# Ethernet.net
KiCad netlist of a schematic drawn in Altium Designer
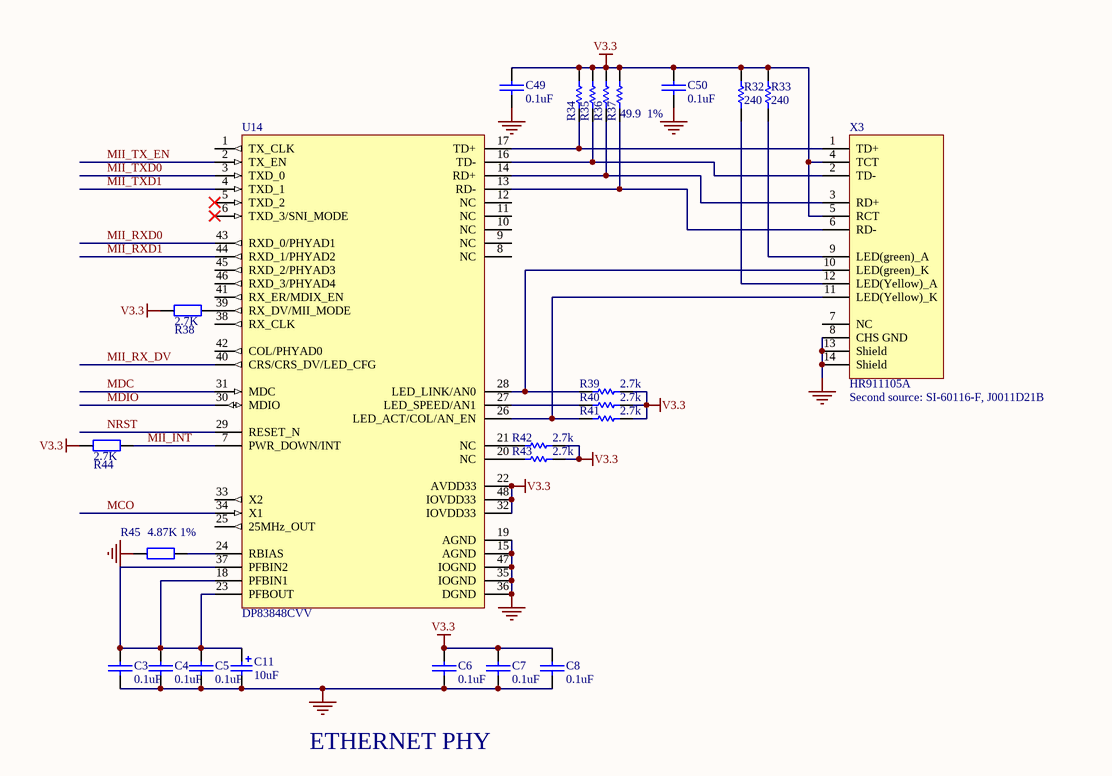
[diagram p0: Ethernet.SchDoc]

(export (version "E")
  (design (tool "Eeschema 10.0.6"))
  (components
    (comp (ref "C3")
      (value "0.1uF")
      (footprint "0603")
      (description "Capacitor")
      (libsource (lib "*") (part "CAP"))
    )
    (comp (ref "C4")
      (value "0.1uF")
      (footprint "0603")
      (description "Capacitor")
      (libsource (lib "*") (part "CAP"))
    )
    (comp (ref "C5")
      (value "0.1uF")
      (footprint "0603")
      (description "Capacitor")
      (libsource (lib "*") (part "CAP"))
    )
    (comp (ref "C6")
      (value "0.1uF")
      (footprint "0603")
      (description "Capacitor")
      (libsource (lib "*") (part "CAP"))
    )
    (comp (ref "C7")
      (value "0.1uF")
      (footprint "0603")
      (description "Capacitor")
      (libsource (lib "*") (part "CAP"))
    )
    (comp (ref "C8")
      (value "0.1uF")
      (footprint "0603")
      (description "Capacitor")
      (libsource (lib "*") (part "CAP"))
    )
    (comp (ref "C11")
      (value "10uF")
      (footprint "0805")
      (description "Polarized Capacitor (Radial)")
      (fields (field (name "PUBLISHER") "Altium Limited"))
      (libsource (lib "Miscellaneous Devices") (part "Cap Pol1"))
    )
    (comp (ref "C49")
      (value "0.1uF")
      (footprint "0603")
      (description "Capacitor")
      (libsource (lib "*") (part "CAP"))
    )
    (comp (ref "C50")
      (value "0.1uF")
      (footprint "0603")
      (description "Capacitor")
      (libsource (lib "*") (part "CAP"))
    )
    (comp (ref "R32")
      (value "240")
      (footprint "0603R")
      (description "Resistor")
      (fields (field (name "PUBLISHER") "Altium Limited"))
      (libsource (lib "Miscellaneous Devices") (part "Res1"))
    )
    (comp (ref "R33")
      (value "240")
      (footprint "0603R")
      (description "Resistor")
      (fields (field (name "PUBLISHER") "Altium Limited"))
      (libsource (lib "Miscellaneous Devices") (part "Res1"))
    )
    (comp (ref "R34")
      (value "49.9  1%")
      (footprint "0603R")
      (description "Resistor")
      (fields (field (name "PUBLISHER") "Altium Limited"))
      (libsource (lib "Miscellaneous Devices") (part "Res1"))
    )
    (comp (ref "R35")
      (value "49.9  1%")
      (footprint "0603R")
      (description "Resistor")
      (fields (field (name "PUBLISHER") "Altium Limited"))
      (libsource (lib "Miscellaneous Devices") (part "Res1"))
    )
    (comp (ref "R36")
      (value "49.9  1%")
      (footprint "0603R")
      (description "Resistor")
      (fields (field (name "PUBLISHER") "Altium Limited"))
      (libsource (lib "Miscellaneous Devices") (part "Res1"))
    )
    (comp (ref "R37")
      (value "49.9  1%")
      (footprint "0603R")
      (description "Resistor")
      (fields (field (name "PUBLISHER") "Altium Limited"))
      (libsource (lib "Miscellaneous Devices") (part "Res1"))
    )
    (comp (ref "R38")
      (value "2.7K")
      (footprint "0603R")
      (description "Resistor")
      (fields (field (name "PUBLISHER") "Altium Limited"))
      (libsource (lib "Miscellaneous Devices") (part "Res2"))
    )
    (comp (ref "R39")
      (value "2.7k")
      (footprint "0603R")
      (description "Resistor")
      (fields (field (name "PUBLISHER") "Altium Limited"))
      (libsource (lib "Miscellaneous Devices") (part "Res1"))
    )
    (comp (ref "R40")
      (value "2.7k")
      (footprint "0603R")
      (description "Resistor")
      (fields (field (name "PUBLISHER") "Altium Limited"))
      (libsource (lib "Miscellaneous Devices") (part "Res1"))
    )
    (comp (ref "R41")
      (value "2.7k")
      (footprint "0603R")
      (description "Resistor")
      (fields (field (name "PUBLISHER") "Altium Limited"))
      (libsource (lib "Miscellaneous Devices") (part "Res1"))
    )
    (comp (ref "R42")
      (value "2.7k")
      (footprint "0603R")
      (description "Resistor")
      (fields (field (name "PUBLISHER") "Altium Limited"))
      (libsource (lib "Miscellaneous Devices") (part "Res1"))
    )
    (comp (ref "R43")
      (value "2.7k")
      (footprint "0603R")
      (description "Resistor")
      (fields (field (name "PUBLISHER") "Altium Limited"))
      (libsource (lib "Miscellaneous Devices") (part "Res1"))
    )
    (comp (ref "R44")
      (value "2.7K")
      (footprint "0603R")
      (description "Resistor")
      (fields (field (name "PUBLISHER") "Altium Limited"))
      (libsource (lib "Miscellaneous Devices") (part "Res2"))
    )
    (comp (ref "R45")
      (value "4.87K 1%")
      (footprint "0603R")
      (description "Resistor")
      (fields (field (name "PUBLISHER") "Altium Limited"))
      (libsource (lib "Miscellaneous Devices") (part "Res2"))
    )
    (comp (ref "U14")
      (value "DP83848CVV")
      (footprint "LQFP48S")
      (libsource (lib "MB784") (part "DP83848CVV"))
    )
    (comp (ref "X3") (value "HR911105A") (footprint "HR911105A") (libsource (lib "MB784") (part "J0011D21B")))
  )
  (nets
    (net (code "1") (name "/MCO") (class "Default")
      (node (ref "U14") (pin "34") (pinfunction "X1_34") (pintype "input"))
    )
    (net (code "2") (name "/MDC") (class "Default")
      (node (ref "U14") (pin "31") (pinfunction "MDC_31") (pintype "input"))
    )
    (net (code "3") (name "/MDIO") (class "Default")
      (node (ref "U14") (pin "30") (pinfunction "MDIO_30") (pintype "bidirectional"))
    )
    (net (code "4") (name "/MII_INT") (class "Default")
      (node (ref "R44") (pin "1") (pinfunction "1_1") (pintype "passive"))
      (node (ref "U14") (pin "7") (pinfunction "PWR_DOWN/INT_7") (pintype "passive"))
    )
    (net (code "5") (name "/MII_RXD0") (class "Default")
      (node (ref "U14") (pin "43") (pinfunction "RXD_0/PHYAD1_43") (pintype "output"))
    )
    (net (code "6") (name "/MII_RXD1") (class "Default")
      (node (ref "U14") (pin "44") (pinfunction "RXD_1/PHYAD2_44") (pintype "output"))
    )
    (net (code "7") (name "/MII_RX_DV") (class "Default")
      (node (ref "U14") (pin "40") (pinfunction "CRS/CRS_DV/LED_CFG_40") (pintype "output"))
    )
    (net (code "8") (name "/MII_TXD0") (class "Default")
      (node (ref "U14") (pin "3") (pinfunction "TXD_0_3") (pintype "input"))
    )
    (net (code "9") (name "/MII_TXD1") (class "Default")
      (node (ref "U14") (pin "4") (pinfunction "TXD_1_4") (pintype "input"))
    )
    (net (code "10") (name "/MII_TX_EN") (class "Default")
      (node (ref "U14") (pin "2") (pinfunction "TX_EN_2") (pintype "input"))
    )
    (net (code "11") (name "/NRST") (class "Default")
      (node (ref "U14") (pin "29") (pinfunction "RESET_N_29") (pintype "passive"))
    )
    (net (code "12") (name "GND") (class "Default")
      (node (ref "C11") (pin "2") (pinfunction "2_2") (pintype "passive"))
      (node (ref "C3") (pin "2") (pinfunction "2_2") (pintype "passive"))
      (node (ref "C4") (pin "1") (pinfunction "1_1") (pintype "passive"))
      (node (ref "C49") (pin "1") (pinfunction "1_1") (pintype "passive"))
      (node (ref "C5") (pin "1") (pinfunction "1_1") (pintype "passive"))
      (node (ref "C50") (pin "1") (pinfunction "1_1") (pintype "passive"))
      (node (ref "C6") (pin "2") (pinfunction "2_2") (pintype "passive"))
      (node (ref "C7") (pin "1") (pinfunction "1_1") (pintype "passive"))
      (node (ref "C8") (pin "1") (pinfunction "1_1") (pintype "passive"))
      (node (ref "R45") (pin "2") (pinfunction "2_2") (pintype "passive"))
      (node (ref "U14") (pin "15") (pinfunction "AGND_15") (pintype "passive"))
      (node (ref "U14") (pin "19") (pinfunction "AGND_19") (pintype "passive"))
      (node (ref "U14") (pin "35") (pinfunction "IOGND_35") (pintype "passive"))
      (node (ref "U14") (pin "36") (pinfunction "DGND_36") (pintype "passive"))
      (node (ref "U14") (pin "47") (pinfunction "IOGND_47") (pintype "passive"))
      (node (ref "X3") (pin "13") (pinfunction "Shield_13") (pintype "passive"))
      (node (ref "X3") (pin "14") (pinfunction "Shield_14") (pintype "passive"))
      (node (ref "X3") (pin "8") (pinfunction "CHS_GND_8") (pintype "passive"))
    )
    (net (code "13") (name "Net-(R42-Pad1)") (class "Default")
      (node (ref "R42") (pin "1") (pinfunction "1_1") (pintype "passive"))
      (node (ref "U14") (pin "21") (pinfunction "NC_21") (pintype "passive"))
    )
    (net (code "14") (name "Net-(R43-Pad1)") (class "Default")
      (node (ref "R43") (pin "1") (pinfunction "1_1") (pintype "passive"))
      (node (ref "U14") (pin "20") (pinfunction "NC_20") (pintype "passive"))
    )
    (net (code "15") (name "Net-(U14-LED_ACT{slash}COL{slash}AN_EN)") (class "Default")
      (node (ref "R41") (pin "1") (pinfunction "1_1") (pintype "passive"))
      (node (ref "U14") (pin "26") (pinfunction "LED_ACT/COL/AN_EN_26") (pintype "passive"))
      (node (ref "X3") (pin "11") (pinfunction "LED(Yellow)_K_11") (pintype "passive"))
    )
    (net (code "16") (name "Net-(U14-LED_LINK{slash}AN0)") (class "Default")
      (node (ref "R39") (pin "1") (pinfunction "1_1") (pintype "passive"))
      (node (ref "U14") (pin "28") (pinfunction "LED_LINK/AN0_28") (pintype "passive"))
      (node (ref "X3") (pin "10") (pinfunction "LED(green)_K_10") (pintype "passive"))
    )
    (net (code "17") (name "Net-(U14-LED_SPEED{slash}AN1)") (class "Default")
      (node (ref "R40") (pin "1") (pinfunction "1_1") (pintype "passive"))
      (node (ref "U14") (pin "27") (pinfunction "LED_SPEED/AN1_27") (pintype "passive"))
    )
    (net (code "18") (name "Net-(U14-PFBIN1)") (class "Default")
      (node (ref "C11") (pin "1") (pinfunction "1_1") (pintype "passive"))
      (node (ref "C3") (pin "1") (pinfunction "1_1") (pintype "passive"))
      (node (ref "C4") (pin "2") (pinfunction "2_2") (pintype "passive"))
      (node (ref "C5") (pin "2") (pinfunction "2_2") (pintype "passive"))
      (node (ref "U14") (pin "18") (pinfunction "PFBIN1_18") (pintype "passive"))
      (node (ref "U14") (pin "23") (pinfunction "PFBOUT_23") (pintype "passive"))
      (node (ref "U14") (pin "37") (pinfunction "PFBIN2_37") (pintype "passive"))
    )
    (net (code "19") (name "Net-(U14-RBIAS)") (class "Default")
      (node (ref "R45") (pin "1") (pinfunction "1_1") (pintype "passive"))
      (node (ref "U14") (pin "24") (pinfunction "RBIAS_24") (pintype "passive"))
    )
    (net (code "20") (name "Net-(U14-RD+)") (class "Default")
      (node (ref "R36") (pin "1") (pinfunction "1_1") (pintype "passive"))
      (node (ref "U14") (pin "14") (pinfunction "RD+_14") (pintype "passive"))
      (node (ref "X3") (pin "3") (pinfunction "RD+_3") (pintype "passive"))
    )
    (net (code "21") (name "Net-(U14-RD-)") (class "Default")
      (node (ref "R37") (pin "1") (pinfunction "1_1") (pintype "passive"))
      (node (ref "U14") (pin "13") (pinfunction "RD-_13") (pintype "passive"))
      (node (ref "X3") (pin "6") (pinfunction "RD-_6") (pintype "passive"))
    )
    (net (code "22") (name "Net-(U14-RX_DV{slash}MII_MODE)") (class "Default")
      (node (ref "R38") (pin "1") (pinfunction "1_1") (pintype "passive"))
      (node (ref "U14") (pin "39") (pinfunction "RX_DV/MII_MODE_39") (pintype "output"))
    )
    (net (code "23") (name "Net-(U14-TD+)") (class "Default")
      (node (ref "R34") (pin "1") (pinfunction "1_1") (pintype "passive"))
      (node (ref "U14") (pin "17") (pinfunction "TD+_17") (pintype "passive"))
      (node (ref "X3") (pin "1") (pinfunction "TD+_1") (pintype "passive"))
    )
    (net (code "24") (name "Net-(U14-TD-)") (class "Default")
      (node (ref "R35") (pin "1") (pinfunction "1_1") (pintype "passive"))
      (node (ref "U14") (pin "16") (pinfunction "TD-_16") (pintype "passive"))
      (node (ref "X3") (pin "2") (pinfunction "TD-_2") (pintype "passive"))
    )
    (net (code "25") (name "Net-(X3-LED(Yellow)_A)") (class "Default")
      (node (ref "R32") (pin "1") (pinfunction "1_1") (pintype "passive"))
      (node (ref "X3") (pin "12") (pinfunction "LED(Yellow)_A_12") (pintype "passive"))
    )
    (net (code "26") (name "Net-(X3-LED(green)_A)") (class "Default")
      (node (ref "R33") (pin "1") (pinfunction "1_1") (pintype "passive"))
      (node (ref "X3") (pin "9") (pinfunction "LED(green)_A_9") (pintype "passive"))
    )
    (net (code "27") (name "V3.3") (class "Default")
      (node (ref "C49") (pin "2") (pinfunction "2_2") (pintype "passive"))
      (node (ref "C50") (pin "2") (pinfunction "2_2") (pintype "passive"))
      (node (ref "C6") (pin "1") (pinfunction "1_1") (pintype "passive"))
      (node (ref "C7") (pin "2") (pinfunction "2_2") (pintype "passive"))
      (node (ref "C8") (pin "2") (pinfunction "2_2") (pintype "passive"))
      (node (ref "R32") (pin "2") (pinfunction "2_2") (pintype "passive"))
      (node (ref "R33") (pin "2") (pinfunction "2_2") (pintype "passive"))
      (node (ref "R34") (pin "2") (pinfunction "2_2") (pintype "passive"))
      (node (ref "R35") (pin "2") (pinfunction "2_2") (pintype "passive"))
      (node (ref "R36") (pin "2") (pinfunction "2_2") (pintype "passive"))
      (node (ref "R37") (pin "2") (pinfunction "2_2") (pintype "passive"))
      (node (ref "R38") (pin "2") (pinfunction "2_2") (pintype "passive"))
      (node (ref "R39") (pin "2") (pinfunction "2_2") (pintype "passive"))
      (node (ref "R40") (pin "2") (pinfunction "2_2") (pintype "passive"))
      (node (ref "R41") (pin "2") (pinfunction "2_2") (pintype "passive"))
      (node (ref "R42") (pin "2") (pinfunction "2_2") (pintype "passive"))
      (node (ref "R43") (pin "2") (pinfunction "2_2") (pintype "passive"))
      (node (ref "R44") (pin "2") (pinfunction "2_2") (pintype "passive"))
      (node (ref "U14") (pin "22") (pinfunction "AVDD33_22") (pintype "passive"))
      (node (ref "U14") (pin "32") (pinfunction "IOVDD33_32") (pintype "passive"))
      (node (ref "U14") (pin "48") (pinfunction "IOVDD33_48") (pintype "passive"))
      (node (ref "X3") (pin "4") (pinfunction "TCT_4") (pintype "passive"))
      (node (ref "X3") (pin "5") (pinfunction "RCT_5") (pintype "passive"))
    )
    (net (code "28") (name "unconnected-(U14-25MHz_OUT-Pad25)") (class "Default")
      (node (ref "U14") (pin "25") (pinfunction "25MHz_OUT_25") (pintype "output"))
    )
    (net (code "29") (name "unconnected-(U14-COL{slash}PHYAD0-Pad42)") (class "Default")
      (node (ref "U14") (pin "42") (pinfunction "COL/PHYAD0_42") (pintype "output"))
    )
    (net (code "30") (name "unconnected-(U14-NC-Pad8)") (class "Default")
      (node (ref "U14") (pin "8") (pinfunction "NC_8") (pintype "passive"))
    )
    (net (code "31") (name "unconnected-(U14-NC-Pad9)") (class "Default")
      (node (ref "U14") (pin "9") (pinfunction "NC_9") (pintype "passive"))
    )
    (net (code "32") (name "unconnected-(U14-NC-Pad10)") (class "Default")
      (node (ref "U14") (pin "10") (pinfunction "NC_10") (pintype "passive"))
    )
    (net (code "33") (name "unconnected-(U14-NC-Pad11)") (class "Default")
      (node (ref "U14") (pin "11") (pinfunction "NC_11") (pintype "passive"))
    )
    (net (code "34") (name "unconnected-(U14-NC-Pad12)") (class "Default")
      (node (ref "U14") (pin "12") (pinfunction "NC_12") (pintype "passive"))
    )
    (net (code "35") (name "unconnected-(U14-RXD_2{slash}PHYAD3-Pad45)") (class "Default")
      (node (ref "U14") (pin "45") (pinfunction "RXD_2/PHYAD3_45") (pintype "output"))
    )
    (net (code "36") (name "unconnected-(U14-RXD_3{slash}PHYAD4-Pad46)") (class "Default")
      (node (ref "U14") (pin "46") (pinfunction "RXD_3/PHYAD4_46") (pintype "output"))
    )
    (net (code "37") (name "unconnected-(U14-RX_CLK-Pad38)") (class "Default")
      (node (ref "U14") (pin "38") (pinfunction "RX_CLK_38") (pintype "output"))
    )
    (net (code "38") (name "unconnected-(U14-RX_ER{slash}MDIX_EN-Pad41)") (class "Default")
      (node (ref "U14") (pin "41") (pinfunction "RX_ER/MDIX_EN_41") (pintype "output"))
    )
    (net (code "39") (name "unconnected-(U14-TXD_2-Pad5)") (class "Default")
      (node (ref "U14") (pin "5") (pinfunction "TXD_2_5") (pintype "input+no_connect"))
    )
    (net (code "40") (name "unconnected-(U14-TXD_3{slash}SNI_MODE-Pad6)") (class "Default")
      (node (ref "U14") (pin "6") (pinfunction "TXD_3/SNI_MODE_6") (pintype "input+no_connect"))
    )
    (net (code "41") (name "unconnected-(U14-TX_CLK-Pad1)") (class "Default")
      (node (ref "U14") (pin "1") (pinfunction "TX_CLK_1") (pintype "output"))
    )
    (net (code "42") (name "unconnected-(U14-X2-Pad33)") (class "Default")
      (node (ref "U14") (pin "33") (pinfunction "X2_33") (pintype "output"))
    )
    (net (code "43") (name "unconnected-(X3-NC-Pad7)") (class "Default")
      (node (ref "X3") (pin "7") (pinfunction "NC_7") (pintype "passive"))
    )
  )
)
